# V40TestAdapter.net
KiCad netlist of a schematic drawn in Altium Designer
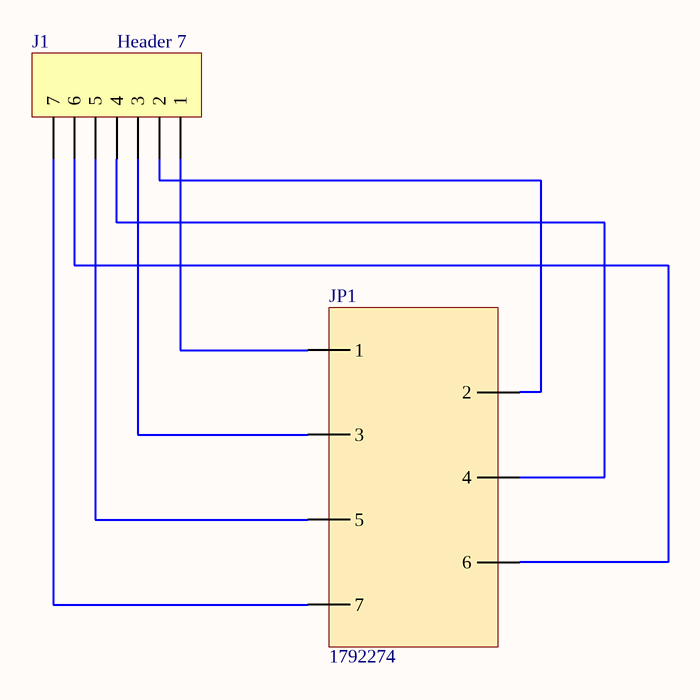
[diagram p0: V40TestAdapter.SchDoc]

(export (version "E")
  (design (tool "Eeschema 10.0.6"))
  (components
    (comp (ref "J1")
      (value "Header 7")
      (footprint "HDR1X7")
      (description "Header, 7-Pin")
      (fields (field (name "PUBLISHER") "Altium Limited"))
      (libsource (lib "Miscellaneous Connectors") (part "Header 7"))
    )
    (comp (ref "JP1")
      (value "1792274")
      (footprint "7P Terminal Block")
      (libsource (lib "V40TestAdapter") (part "PCB Terminal Block"))
    )
  )
  (nets
    (net (code "1") (name "Net-(J1-Pad1)") (class "Default")
      (node (ref "J1") (pin "1") (pinfunction "1_1") (pintype "passive"))
      (node (ref "JP1") (pin "1") (pinfunction "1_1") (pintype "passive"))
    )
    (net (code "2") (name "Net-(J1-Pad2)") (class "Default")
      (node (ref "J1") (pin "2") (pinfunction "2_2") (pintype "passive"))
      (node (ref "JP1") (pin "2") (pinfunction "2_2") (pintype "passive"))
    )
    (net (code "3") (name "Net-(J1-Pad3)") (class "Default")
      (node (ref "J1") (pin "3") (pinfunction "3_3") (pintype "passive"))
      (node (ref "JP1") (pin "3") (pinfunction "3_3") (pintype "passive"))
    )
    (net (code "4") (name "Net-(J1-Pad4)") (class "Default")
      (node (ref "J1") (pin "4") (pinfunction "4_4") (pintype "passive"))
      (node (ref "JP1") (pin "4") (pinfunction "4_4") (pintype "passive"))
    )
    (net (code "5") (name "Net-(J1-Pad5)") (class "Default")
      (node (ref "J1") (pin "5") (pinfunction "5_5") (pintype "passive"))
      (node (ref "JP1") (pin "5") (pinfunction "5_5") (pintype "passive"))
    )
    (net (code "6") (name "Net-(J1-Pad6)") (class "Default")
      (node (ref "J1") (pin "6") (pinfunction "6_6") (pintype "passive"))
      (node (ref "JP1") (pin "6") (pinfunction "6_6") (pintype "passive"))
    )
    (net (code "7") (name "Net-(J1-Pad7)") (class "Default")
      (node (ref "J1") (pin "7") (pinfunction "7_7") (pintype "passive"))
      (node (ref "JP1") (pin "7") (pinfunction "7_7") (pintype "passive"))
    )
  )
)
